# max1749-breakout.net
KiCad netlist of a schematic drawn in EAGLE
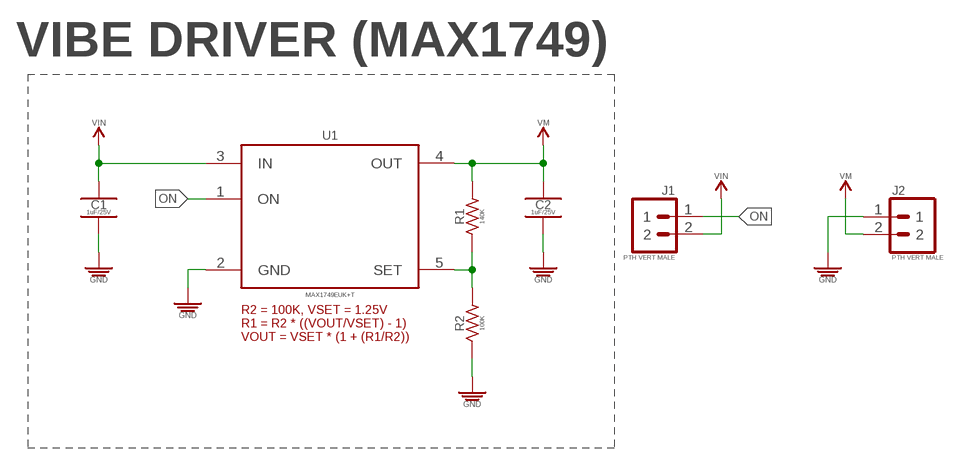
[diagram p0: schematic, sheet 1]

(export (version "E")
  (design (tool "Eeschema 10.0.6"))
  (components
    (comp (ref "C1")
      (value "1uF/25V")
      (footprint "eagle-import:CAPC1005X55_SMD-0402")
      (fields (field (name "MFR") "TDK Corporation") (field (name "MPN") "CGB2A1X5R1E105K033BC"))
      (libsource (lib "eagle-import") (part "1UF_CER_SMD-0402_25V-10%"))
    )
    (comp (ref "C2")
      (value "1uF/25V")
      (footprint "eagle-import:CAPC1005X55_SMD-0402")
      (fields (field (name "MFR") "TDK Corporation") (field (name "MPN") "CGB2A1X5R1E105K033BC"))
      (libsource (lib "eagle-import") (part "1UF_CER_SMD-0402_25V-10%"))
    )
    (comp (ref "J1")
      (value "PTH VERT MALE")
      (footprint "eagle-import:HDRV2W64P254_1X2_508X254X838B")
      (fields (field (name "MFR") "Sullins Connector Solutions") (field (name "MPN") "PEC02SAAN"))
      (libsource (lib "eagle-import") (part "1X02_PTH_VERT_MALE_2.54MM"))
    )
    (comp (ref "J2")
      (value "PTH VERT MALE")
      (footprint "eagle-import:HDRV2W64P254_1X2_508X254X838B")
      (fields (field (name "MFR") "Sullins Connector Solutions") (field (name "MPN") "PEC02SAAN"))
      (libsource (lib "eagle-import") (part "1X02_PTH_VERT_MALE_2.54MM"))
    )
    (comp (ref "R1")
      (value "140K")
      (footprint "eagle-import:RESC1005X35_SMD-0402")
      (fields (field (name "MFR") "Yageo") (field (name "MPN") "RC0402FR-07140KL"))
      (libsource (lib "eagle-import") (part "140KΩ_SMD-0402_1/16W-1%"))
    )
    (comp (ref "R2")
      (value "100K")
      (footprint "eagle-import:RESC1005X35_SMD-0402")
      (fields (field (name "MFR") "Yageo") (field (name "MPN") "RC0402JR-07100KL"))
      (libsource (lib "eagle-import") (part "100KΩ_SMD-0402_1/16W_5%"))
    )
    (comp (ref "U1")
      (value "MAX1749EUK+T")
      (footprint "eagle-import:SOT95P280X117-5N")
      (fields (field (name "MFR") "Maxim Integrated"))
      (libsource (lib "eagle-import") (part "MAX1749_MAX1749EUK-T"))
    )
  )
  (nets
    (net (code "1") (name "GND") (class "Default")
      (node (ref "C1") (pin "2") (pinfunction "2_2") (pintype "passive"))
      (node (ref "C2") (pin "2") (pinfunction "2_2") (pintype "passive"))
      (node (ref "J2") (pin "1") (pinfunction "1_1") (pintype "passive"))
      (node (ref "R2") (pin "1") (pinfunction "1_1") (pintype "passive"))
      (node (ref "U1") (pin "2") (pinfunction "GND_2") (pintype "power_in"))
    )
    (net (code "2") (name "Net-(U1-SET)") (class "Default")
      (node (ref "R1") (pin "1") (pinfunction "1_1") (pintype "passive"))
      (node (ref "R2") (pin "2") (pinfunction "2_2") (pintype "passive"))
      (node (ref "U1") (pin "5") (pinfunction "SET_5") (pintype "bidirectional"))
    )
    (net (code "3") (name "ON") (class "Default")
      (node (ref "J1") (pin "1") (pinfunction "1_1") (pintype "passive"))
      (node (ref "U1") (pin "1") (pinfunction "ON_1") (pintype "bidirectional"))
    )
    (net (code "4") (name "VIN") (class "Default")
      (node (ref "C1") (pin "1") (pinfunction "1_1") (pintype "passive"))
      (node (ref "J1") (pin "2") (pinfunction "2_2") (pintype "passive"))
      (node (ref "U1") (pin "3") (pinfunction "IN_3") (pintype "power_in"))
    )
    (net (code "5") (name "VM") (class "Default")
      (node (ref "C2") (pin "1") (pinfunction "1_1") (pintype "passive"))
      (node (ref "J2") (pin "2") (pinfunction "2_2") (pintype "passive"))
      (node (ref "R1") (pin "2") (pinfunction "2_2") (pintype "passive"))
      (node (ref "U1") (pin "4") (pinfunction "OUT_4") (pintype "bidirectional"))
    )
  )
)
